# Adafruit_FONA_SIM5320_3G_Breakout.net
KiCad netlist of a schematic drawn in EAGLE
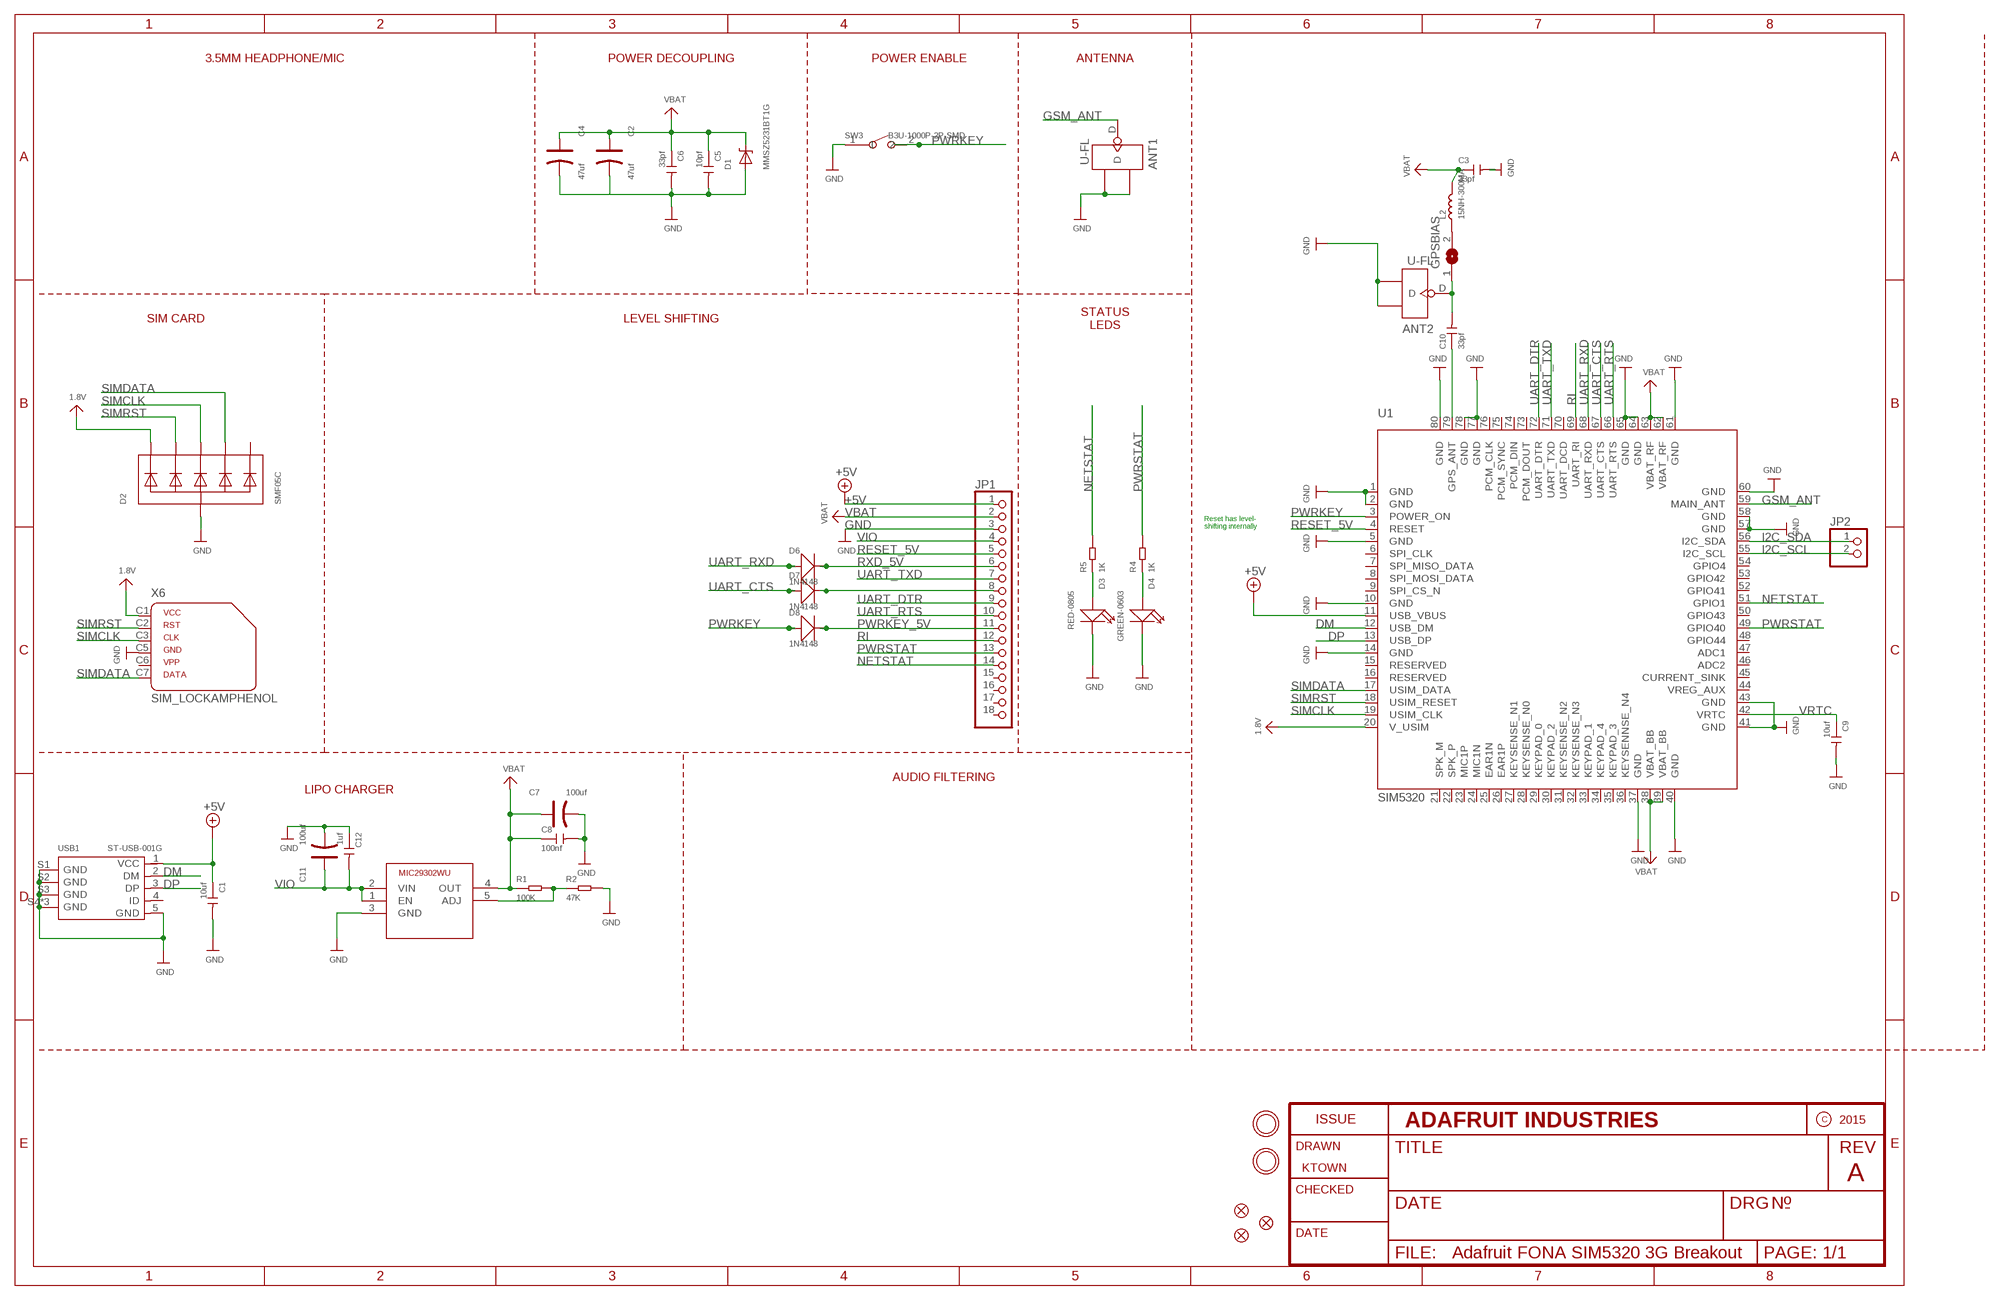
[diagram p0: schematic, sheet 1]

(export (version "E")
  (design (tool "Eeschema 10.0.6"))
  (components
    (comp (ref "ANT1")
      (value "U-FL")
      (footprint "eagle-import:U-FL3P-SMD-2.6X2.6X1.0MM")
      (libsource (lib "eagle-import") (part "ANTENNA-CONN-U-FL(3P)"))
    )
    (comp (ref "ANT2")
      (value "U-FL")
      (footprint "eagle-import:U-FL3P-SMD-2.6X2.6X1.0MM")
      (libsource (lib "eagle-import") (part "ANTENNA-CONN-U-FL(3P)"))
    )
    (comp (ref "C1")
      (value "10uf")
      (footprint "eagle-import:C0603")
      (fields (field (name "MPN") "CC0603KRX5R6BB106"))
      (libsource (lib "eagle-import") (part "CERAMIC-10UF-10V-10%-X5R(0603)"))
    )
    (comp (ref "C2")
      (value "47uf")
      (footprint "eagle-import:AVX-B")
      (fields (field (name "MPN") "TAJB476K010RNJ"))
      (libsource (lib "eagle-import") (part "TANTALUM-SMD-47UF-16V-10%(AVX-B)"))
    )
    (comp (ref "C3")
      (value "33pf")
      (footprint "eagle-import:C0402")
      (fields (field (name "MPN") "CC0402JRNPO9BN330"))
      (libsource (lib "eagle-import") (part "CERAMIC-33PF-50V-5%-NPO(0402)"))
    )
    (comp (ref "C4")
      (value "47uf")
      (footprint "eagle-import:AVX-B")
      (fields (field (name "MPN") "TAJB476K010RNJ"))
      (libsource (lib "eagle-import") (part "TANTALUM-SMD-47UF-16V-10%(AVX-B)"))
    )
    (comp (ref "C5")
      (value "10pf")
      (footprint "eagle-import:C0402")
      (fields (field (name "MPN") "CC0402JRNPO9BN100"))
      (libsource (lib "eagle-import") (part "CERAMIC-10PF-50V-5%-NPO(0402)"))
    )
    (comp (ref "C6")
      (value "33pf")
      (footprint "eagle-import:C0402")
      (fields (field (name "MPN") "CC0402JRNPO9BN330"))
      (libsource (lib "eagle-import") (part "CERAMIC-33PF-50V-5%-NPO(0402)"))
    )
    (comp (ref "C7")
      (value "100uf")
      (footprint "eagle-import:AVX-B")
      (fields (field (name "MPN") "TAJB107M010#NJ"))
      (libsource (lib "eagle-import") (part "TANTALUM-SMD-100UF-10V(AVX-B)"))
    )
    (comp (ref "C8")
      (value "100nf")
      (footprint "eagle-import:C0402")
      (fields (field (name "MPN") "CC0402KRX7R8BB104"))
      (libsource (lib "eagle-import") (part "CERAMIC-100NF-25V-10%-X7R(0402)"))
    )
    (comp (ref "C9")
      (value "10uf")
      (footprint "eagle-import:C0805")
      (fields (field (name "MPN") "CC0805KKX5R8BB106"))
      (libsource (lib "eagle-import") (part "CERAMIC-10UF-25V-10%-X5R(0805)"))
    )
    (comp (ref "C10")
      (value "33pf")
      (footprint "eagle-import:C0402")
      (fields (field (name "MPN") "CC0402JRNPO9BN330"))
      (libsource (lib "eagle-import") (part "CERAMIC-33PF-50V-5%-NPO(0402)"))
    )
    (comp (ref "C11")
      (value "100uf")
      (footprint "eagle-import:AVX-B")
      (fields (field (name "MPN") "TAJB107M010#NJ"))
      (libsource (lib "eagle-import") (part "TANTALUM-SMD-100UF-10V(AVX-B)"))
    )
    (comp (ref "C12")
      (value "1uf")
      (footprint "eagle-import:C0603")
      (fields (field (name "MPN") "CC0603KRX7R8BB105"))
      (libsource (lib "eagle-import") (part "CERAMIC-1UF-25V-10%-X7R(0603)"))
    )
    (comp (ref "D1")
      (value "MMSZ5231BT1G")
      (footprint "eagle-import:SOD-123")
      (libsource (lib "eagle-import") (part "DIODE-ZENERSOD123"))
    )
    (comp (ref "D2")
      (value "SMF05C")
      (footprint "eagle-import:SOT363")
      (libsource (lib "eagle-import") (part "TVSARRAY_5LANE"))
    )
    (comp (ref "D3")
      (value "RED-0805")
      (footprint "eagle-import:LED-0805")
      (fields (field (name "MPN") "17-215SURC/S530-A2/TR8"))
      (libsource (lib "eagle-import") (part "SMD-LED-CLEAR-RED(0805)"))
    )
    (comp (ref "D4")
      (value "GREEN-0603")
      (footprint "eagle-import:LED-0603")
      (fields (field (name "MPN") "19-217-G7C-AN1P2-3T"))
      (libsource (lib "eagle-import") (part "SMD-LED-CLEAR-GREEN(0603)"))
    )
    (comp (ref "D6")
      (value "1N4148")
      (footprint "eagle-import:LL-34")
      (libsource (lib "eagle-import") (part "SMD-DIODE-SWITCH-1N4148(LL-34)"))
    )
    (comp (ref "D7")
      (value "1N4148")
      (footprint "eagle-import:LL-34")
      (libsource (lib "eagle-import") (part "SMD-DIODE-SWITCH-1N4148(LL-34)"))
    )
    (comp (ref "D8")
      (value "1N4148")
      (footprint "eagle-import:LL-34")
      (libsource (lib "eagle-import") (part "SMD-DIODE-SWITCH-1N4148(LL-34)"))
    )
    (comp (ref "FID1")
      (value "FIDUCIAL\"\"")
      (footprint "eagle-import:FIDUCIAL_1MM")
      (libsource (lib "eagle-import") (part "FIDUCIAL{dblquote}{dblquote}"))
    )
    (comp (ref "FID4")
      (value "FIDUCIAL\"\"")
      (footprint "eagle-import:FIDUCIAL_1MM")
      (libsource (lib "eagle-import") (part "FIDUCIAL{dblquote}{dblquote}"))
    )
    (comp (ref "FID5")
      (value "FIDUCIAL\"\"")
      (footprint "eagle-import:FIDUCIAL_1MM")
      (libsource (lib "eagle-import") (part "FIDUCIAL{dblquote}{dblquote}"))
    )
    (comp (ref "GPSBIAS")
      (value "SOLDERJUMPER")
      (footprint "eagle-import:SOLDERJUMPER_ARROW_NOPASTE")
      (libsource (lib "eagle-import") (part "SOLDERJUMPER"))
    )
    (comp (ref "IC1")
      (value "MIC29302WU")
      (footprint "eagle-import:TO263-5")
      (fields (field (name "MF") "Microchip"))
      (libsource (lib "eagle-import") (part "MIC29302WU"))
    )
    (comp (ref "JP1")
      (value "HEADER-1X18")
      (footprint "eagle-import:1X18_ROUND70")
      (libsource (lib "eagle-import") (part "HEADER-1X18"))
    )
    (comp (ref "JP2")
      (value "HEADER-1X2ROUND")
      (footprint "eagle-import:1X02_ROUND")
      (libsource (lib "eagle-import") (part "HEADER-1X2ROUND"))
    )
    (comp (ref "L2")
      (value "15NH-300MA")
      (footprint "eagle-import:L0402")
      (fields (field (name "MPN") "LQG15HS15NJ02"))
      (libsource (lib "eagle-import") (part "SMD-INDUCTOR-15NH-5%-300MA(0402)"))
    )
    (comp (ref "R1")
      (value "100K")
      (footprint "eagle-import:R0603")
      (fields (field (name "MPN") "RC0603FR-07100KL"))
      (libsource (lib "eagle-import") (part "SMD-RES-100K-1%-1/10W(0603)"))
    )
    (comp (ref "R2")
      (value "47K")
      (footprint "eagle-import:R0603")
      (fields (field (name "MPN") "RC0603JR-0747KL"))
      (libsource (lib "eagle-import") (part "SMD-RES-47K-5%-1/10W(0603)"))
    )
    (comp (ref "R4")
      (value "1K")
      (footprint "eagle-import:R0603")
      (fields (field (name "MPN") "RC0603FR-071KL"))
      (libsource (lib "eagle-import") (part "SMD-RES-1K-1%-1/10W(0603)"))
    )
    (comp (ref "R5")
      (value "1K")
      (footprint "eagle-import:R0603")
      (fields (field (name "MPN") "RC0603FR-071KL"))
      (libsource (lib "eagle-import") (part "SMD-RES-1K-1%-1/10W(0603)"))
    )
    (comp (ref "SW3")
      (value "B3U-1000P-2P-SMD")
      (footprint "eagle-import:SW2-2.6-3.0X2.5X1.2+0.4MM")
      (libsource (lib "eagle-import") (part "SMD-BUTTON(2P-3.0X2.5X1.2+0.4MM)-B3U-1000P-2P-SMD"))
    )
    (comp (ref "U$33")
      (value "MOUNTINGHOLE2.5")
      (footprint "eagle-import:MOUNTINGHOLE_2.5_PLATED")
      (libsource (lib "eagle-import") (part "MOUNTINGHOLE2.5"))
    )
    (comp (ref "U$34")
      (value "MOUNTINGHOLE2.5")
      (footprint "eagle-import:MOUNTINGHOLE_2.5_PLATED")
      (libsource (lib "eagle-import") (part "MOUNTINGHOLE2.5"))
    )
    (comp (ref "U1")
      (value "SIM5320")
      (footprint "eagle-import:SIM5320")
      (libsource (lib "eagle-import") (part "GSM_SIM5320_LITERAL"))
    )
    (comp (ref "USB1")
      (value "ST-USB-001G")
      (footprint "eagle-import:MICRO-USB5+4P-SMD-0.65-B")
      (libsource (lib "eagle-import") (part "MICRO-USB-SMD-B-WITHOUT-POST-W/P(ST-USB-001G)"))
    )
    (comp (ref "X6")
      (value "SIM_LOCKAMPHENOL")
      (footprint "eagle-import:C707_10M006_512_2")
      (libsource (lib "eagle-import") (part "SIM_LOCKAMPHENOL"))
    )
  )
  (nets
    (net (code "1") (name "+5V") (class "Default")
      (node (ref "C1") (pin "1") (pinfunction "1_1") (pintype "passive"))
      (node (ref "JP1") (pin "1") (pinfunction "1_1") (pintype "passive"))
      (node (ref "U1") (pin "11") (pinfunction "USB_VBUS_11") (pintype "bidirectional"))
      (node (ref "USB1") (pin "1") (pinfunction "VCC_1") (pintype "bidirectional"))
    )
    (net (code "2") (name "/DM") (class "Default")
      (node (ref "U1") (pin "12") (pinfunction "USB_DM_12") (pintype "bidirectional"))
      (node (ref "USB1") (pin "2") (pinfunction "DM_2") (pintype "bidirectional"))
    )
    (net (code "3") (name "/DP") (class "Default")
      (node (ref "U1") (pin "13") (pinfunction "USB_DP_13") (pintype "bidirectional"))
      (node (ref "USB1") (pin "3") (pinfunction "DP_3") (pintype "bidirectional"))
    )
    (net (code "4") (name "/GSM_ANT") (class "Default")
      (node (ref "ANT1") (pin "D") (pinfunction "D_D") (pintype "bidirectional"))
      (node (ref "U1") (pin "59") (pinfunction "MAIN_ANT_59") (pintype "bidirectional"))
    )
    (net (code "5") (name "/I2C_SCL") (class "Default")
      (node (ref "JP2") (pin "2") (pinfunction "2_2") (pintype "passive"))
      (node (ref "U1") (pin "55") (pinfunction "I2C_SCL_55") (pintype "bidirectional"))
    )
    (net (code "6") (name "/I2C_SDA") (class "Default")
      (node (ref "JP2") (pin "1") (pinfunction "1_1") (pintype "passive"))
      (node (ref "U1") (pin "56") (pinfunction "I2C_SDA_56") (pintype "bidirectional"))
    )
    (net (code "7") (name "/NETSTAT") (class "Default")
      (node (ref "JP1") (pin "14") (pinfunction "14_14") (pintype "passive"))
      (node (ref "R5") (pin "2") (pinfunction "2_2") (pintype "passive"))
      (node (ref "U1") (pin "51") (pinfunction "GPIO1_51") (pintype "bidirectional"))
    )
    (net (code "8") (name "/PWRKEY") (class "Default")
      (node (ref "D8") (pin "A") (pinfunction "+_A") (pintype "passive"))
      (node (ref "SW3") (pin "2") (pinfunction "2_2") (pintype "bidirectional"))
      (node (ref "U1") (pin "3") (pinfunction "POWER_ON_3") (pintype "bidirectional"))
    )
    (net (code "9") (name "/PWRKEY_5V") (class "Default")
      (node (ref "D8") (pin "C") (pinfunction "-_C") (pintype "passive"))
      (node (ref "JP1") (pin "11") (pinfunction "11_11") (pintype "passive"))
    )
    (net (code "10") (name "/PWRSTAT") (class "Default")
      (node (ref "JP1") (pin "13") (pinfunction "13_13") (pintype "passive"))
      (node (ref "R4") (pin "2") (pinfunction "2_2") (pintype "passive"))
      (node (ref "U1") (pin "49") (pinfunction "GPIO40_49") (pintype "bidirectional"))
    )
    (net (code "11") (name "/RESET_5V") (class "Default")
      (node (ref "JP1") (pin "5") (pinfunction "5_5") (pintype "passive"))
      (node (ref "U1") (pin "4") (pinfunction "RESET_4") (pintype "bidirectional"))
    )
    (net (code "12") (name "/RI") (class "Default")
      (node (ref "JP1") (pin "12") (pinfunction "12_12") (pintype "passive"))
      (node (ref "U1") (pin "69") (pinfunction "UART_RI_69") (pintype "bidirectional"))
    )
    (net (code "13") (name "/RXD_5V") (class "Default")
      (node (ref "D6") (pin "C") (pinfunction "-_C") (pintype "passive"))
      (node (ref "JP1") (pin "6") (pinfunction "6_6") (pintype "passive"))
    )
    (net (code "14") (name "/SIMCLK") (class "Default")
      (node (ref "D2") (pin "4") (pinfunction "C3_4") (pintype "passive"))
      (node (ref "U1") (pin "19") (pinfunction "USIM_CLK_19") (pintype "bidirectional"))
      (node (ref "X6") (pin "C3") (pinfunction "3_C3") (pintype "passive"))
    )
    (net (code "15") (name "/SIMDATA") (class "Default")
      (node (ref "D2") (pin "5") (pinfunction "C4_5") (pintype "passive"))
      (node (ref "U1") (pin "17") (pinfunction "USIM_DATA_17") (pintype "bidirectional"))
      (node (ref "X6") (pin "C7") (pinfunction "6_C7") (pintype "passive"))
    )
    (net (code "16") (name "/SIMRST") (class "Default")
      (node (ref "D2") (pin "3") (pinfunction "C2_3") (pintype "passive"))
      (node (ref "U1") (pin "18") (pinfunction "USIM_RESET_18") (pintype "bidirectional"))
      (node (ref "X6") (pin "C2") (pinfunction "2_C2") (pintype "passive"))
    )
    (net (code "17") (name "/UART_CTS") (class "Default")
      (node (ref "D7") (pin "A") (pinfunction "+_A") (pintype "passive"))
      (node (ref "U1") (pin "67") (pinfunction "UART_CTS_67") (pintype "bidirectional"))
    )
    (net (code "18") (name "/UART_DTR") (class "Default")
      (node (ref "JP1") (pin "9") (pinfunction "9_9") (pintype "passive"))
      (node (ref "U1") (pin "72") (pinfunction "UART_DTR_72") (pintype "bidirectional"))
    )
    (net (code "19") (name "/UART_RTS") (class "Default")
      (node (ref "JP1") (pin "10") (pinfunction "10_10") (pintype "passive"))
      (node (ref "U1") (pin "66") (pinfunction "UART_RTS_66") (pintype "bidirectional"))
    )
    (net (code "20") (name "/UART_RXD") (class "Default")
      (node (ref "D6") (pin "A") (pinfunction "+_A") (pintype "passive"))
      (node (ref "U1") (pin "68") (pinfunction "UART_RXD_68") (pintype "bidirectional"))
    )
    (net (code "21") (name "/UART_TXD") (class "Default")
      (node (ref "JP1") (pin "7") (pinfunction "7_7") (pintype "passive"))
      (node (ref "U1") (pin "71") (pinfunction "UART_TXD_71") (pintype "bidirectional"))
    )
    (net (code "22") (name "/VIO") (class "Default")
      (node (ref "C11") (pin "+") (pinfunction "+_+") (pintype "passive"))
      (node (ref "C12") (pin "2") (pinfunction "2_2") (pintype "passive"))
      (node (ref "IC1") (pin "1") (pinfunction "EN_1") (pintype "bidirectional"))
      (node (ref "IC1") (pin "2") (pinfunction "VIN_2") (pintype "bidirectional"))
      (node (ref "JP1") (pin "4") (pinfunction "4_4") (pintype "passive"))
    )
    (net (code "23") (name "/VRTC") (class "Default")
      (node (ref "C9") (pin "1") (pinfunction "1_1") (pintype "passive"))
      (node (ref "U1") (pin "42") (pinfunction "VRTC_42") (pintype "bidirectional"))
    )
    (net (code "24") (name "1.8V") (class "Default")
      (node (ref "D2") (pin "1") (pinfunction "C1_1") (pintype "passive"))
      (node (ref "U1") (pin "20") (pinfunction "V_USIM_20") (pintype "bidirectional"))
      (node (ref "X6") (pin "C1") (pinfunction "1_C1") (pintype "passive"))
    )
    (net (code "25") (name "GND") (class "Default")
      (node (ref "ANT1") (pin "GND1") (pinfunction "GND1_GND1") (pintype "bidirectional"))
      (node (ref "ANT1") (pin "GND2") (pinfunction "GND2_GND2") (pintype "bidirectional"))
      (node (ref "ANT2") (pin "GND1") (pinfunction "GND1_GND1") (pintype "bidirectional"))
      (node (ref "ANT2") (pin "GND2") (pinfunction "GND2_GND2") (pintype "bidirectional"))
      (node (ref "C1") (pin "2") (pinfunction "2_2") (pintype "passive"))
      (node (ref "C11") (pin "-") (pinfunction "-_-") (pintype "passive"))
      (node (ref "C12") (pin "1") (pinfunction "1_1") (pintype "passive"))
      (node (ref "C2") (pin "-") (pinfunction "-_-") (pintype "passive"))
      (node (ref "C3") (pin "2") (pinfunction "2_2") (pintype "passive"))
      (node (ref "C4") (pin "-") (pinfunction "-_-") (pintype "passive"))
      (node (ref "C5") (pin "2") (pinfunction "2_2") (pintype "passive"))
      (node (ref "C6") (pin "2") (pinfunction "2_2") (pintype "passive"))
      (node (ref "C7") (pin "-") (pinfunction "-_-") (pintype "passive"))
      (node (ref "C8") (pin "2") (pinfunction "2_2") (pintype "passive"))
      (node (ref "C9") (pin "2") (pinfunction "2_2") (pintype "passive"))
      (node (ref "D1") (pin "A") (pinfunction "A_A") (pintype "passive"))
      (node (ref "D2") (pin "2") (pinfunction "A_2") (pintype "passive"))
      (node (ref "D3") (pin "-") (pinfunction "-_-") (pintype "passive"))
      (node (ref "D4") (pin "-") (pinfunction "-_-") (pintype "passive"))
      (node (ref "IC1") (pin "3") (pinfunction "GND_3") (pintype "bidirectional"))
      (node (ref "JP1") (pin "3") (pinfunction "3_3") (pintype "passive"))
      (node (ref "R2") (pin "2") (pinfunction "2_2") (pintype "passive"))
      (node (ref "SW3") (pin "1") (pinfunction "1_1") (pintype "bidirectional"))
      (node (ref "U1") (pin "1") (pinfunction "GND_1") (pintype "bidirectional"))
      (node (ref "U1") (pin "10") (pinfunction "GND_10") (pintype "bidirectional"))
      (node (ref "U1") (pin "14") (pinfunction "GND_14") (pintype "bidirectional"))
      (node (ref "U1") (pin "2") (pinfunction "GND_2") (pintype "bidirectional"))
      (node (ref "U1") (pin "37") (pinfunction "GND_37") (pintype "bidirectional"))
      (node (ref "U1") (pin "40") (pinfunction "GND_40") (pintype "bidirectional"))
      (node (ref "U1") (pin "41") (pinfunction "GND_41") (pintype "bidirectional"))
      (node (ref "U1") (pin "43") (pinfunction "GND_43") (pintype "bidirectional"))
      (node (ref "U1") (pin "5") (pinfunction "GND_5") (pintype "bidirectional"))
      (node (ref "U1") (pin "57") (pinfunction "GND_57") (pintype "bidirectional"))
      (node (ref "U1") (pin "58") (pinfunction "GND_58") (pintype "bidirectional"))
      (node (ref "U1") (pin "60") (pinfunction "GND_60") (pintype "bidirectional"))
      (node (ref "U1") (pin "61") (pinfunction "GND_61") (pintype "bidirectional"))
      (node (ref "U1") (pin "64") (pinfunction "GND_64") (pintype "bidirectional"))
      (node (ref "U1") (pin "65") (pinfunction "GND_65") (pintype "bidirectional"))
      (node (ref "U1") (pin "77") (pinfunction "GND_77") (pintype "bidirectional"))
      (node (ref "U1") (pin "78") (pinfunction "GND_78") (pintype "bidirectional"))
      (node (ref "U1") (pin "80") (pinfunction "GND_80") (pintype "bidirectional"))
      (node (ref "USB1") (pin "5") (pinfunction "GND_5") (pintype "bidirectional"))
      (node (ref "USB1") (pin "S1") (pinfunction "GND_S1") (pintype "bidirectional"))
      (node (ref "USB1") (pin "S2") (pinfunction "GND_S2") (pintype "bidirectional"))
      (node (ref "USB1") (pin "S3") (pinfunction "GND_S3") (pintype "bidirectional"))
      (node (ref "USB1") (pin "S4") (pinfunction "GND_S4") (pintype "bidirectional"))
      (node (ref "USB1") (pin "S5") (pinfunction "GND_S5") (pintype "bidirectional"))
      (node (ref "USB1") (pin "S6") (pinfunction "GND_S6") (pintype "bidirectional"))
      (node (ref "X6") (pin "C5") (pinfunction "4_C5") (pintype "passive"))
    )
    (net (code "26") (name "Net-(ANT2-PadD)") (class "Default")
      (node (ref "ANT2") (pin "D") (pinfunction "D_D") (pintype "bidirectional"))
      (node (ref "C10") (pin "2") (pinfunction "2_2") (pintype "passive"))
      (node (ref "GPSBIAS") (pin "1") (pinfunction "1_1") (pintype "passive"))
    )
    (net (code "27") (name "Net-(D3-Pad+)") (class "Default")
      (node (ref "D3") (pin "+") (pinfunction "+_+") (pintype "passive"))
      (node (ref "R5") (pin "1") (pinfunction "1_1") (pintype "passive"))
    )
    (net (code "28") (name "Net-(D4-Pad+)") (class "Default")
      (node (ref "D4") (pin "+") (pinfunction "+_+") (pintype "passive"))
      (node (ref "R4") (pin "1") (pinfunction "1_1") (pintype "passive"))
    )
    (net (code "29") (name "Net-(D7--)") (class "Default")
      (node (ref "D7") (pin "C") (pinfunction "-_C") (pintype "passive"))
      (node (ref "JP1") (pin "8") (pinfunction "8_8") (pintype "passive"))
    )
    (net (code "30") (name "Net-(GPSBIAS-Pad2)") (class "Default")
      (node (ref "GPSBIAS") (pin "2") (pinfunction "2_2") (pintype "passive"))
      (node (ref "L2") (pin "1") (pinfunction "1_1") (pintype "passive"))
    )
    (net (code "31") (name "Net-(IC1-ADJ)") (class "Default")
      (node (ref "IC1") (pin "5") (pinfunction "ADJ_5") (pintype "bidirectional"))
      (node (ref "R1") (pin "2") (pinfunction "2_2") (pintype "passive"))
      (node (ref "R2") (pin "1") (pinfunction "1_1") (pintype "passive"))
    )
    (net (code "32") (name "Net-(U1-GPS_ANT)") (class "Default")
      (node (ref "C10") (pin "1") (pinfunction "1_1") (pintype "passive"))
      (node (ref "U1") (pin "79") (pinfunction "GPS_ANT_79") (pintype "bidirectional"))
    )
    (net (code "33") (name "VBAT") (class "Default")
      (node (ref "C2") (pin "+") (pinfunction "+_+") (pintype "passive"))
      (node (ref "C3") (pin "1") (pinfunction "1_1") (pintype "passive"))
      (node (ref "C4") (pin "+") (pinfunction "+_+") (pintype "passive"))
      (node (ref "C5") (pin "1") (pinfunction "1_1") (pintype "passive"))
      (node (ref "C6") (pin "1") (pinfunction "1_1") (pintype "passive"))
      (node (ref "C7") (pin "+") (pinfunction "+_+") (pintype "passive"))
      (node (ref "C8") (pin "1") (pinfunction "1_1") (pintype "passive"))
      (node (ref "D1") (pin "C") (pinfunction "C_C") (pintype "passive"))
      (node (ref "IC1") (pin "4") (pinfunction "OUT_4") (pintype "bidirectional"))
      (node (ref "JP1") (pin "2") (pinfunction "2_2") (pintype "passive"))
      (node (ref "L2") (pin "2") (pinfunction "2_2") (pintype "passive"))
      (node (ref "R1") (pin "1") (pinfunction "1_1") (pintype "passive"))
      (node (ref "U1") (pin "38") (pinfunction "VBAT_BB_38") (pintype "bidirectional"))
      (node (ref "U1") (pin "39") (pinfunction "VBAT_BB_39") (pintype "bidirectional"))
      (node (ref "U1") (pin "62") (pinfunction "VBAT_RF_62") (pintype "bidirectional"))
      (node (ref "U1") (pin "63") (pinfunction "VBAT_RF_63") (pintype "bidirectional"))
    )
    (net (code "34") (name "unconnected-(D2-C5-Pad6)") (class "Default")
      (node (ref "D2") (pin "6") (pinfunction "C5_6") (pintype "passive"))
    )
    (net (code "35") (name "unconnected-(JP1-Pad15)") (class "Default")
      (node (ref "JP1") (pin "15") (pinfunction "15_15") (pintype "passive"))
    )
    (net (code "36") (name "unconnected-(JP1-Pad16)") (class "Default")
      (node (ref "JP1") (pin "16") (pinfunction "16_16") (pintype "passive"))
    )
    (net (code "37") (name "unconnected-(JP1-Pad17)") (class "Default")
      (node (ref "JP1") (pin "17") (pinfunction "17_17") (pintype "passive"))
    )
    (net (code "38") (name "unconnected-(JP1-Pad18)") (class "Default")
      (node (ref "JP1") (pin "18") (pinfunction "18_18") (pintype "passive"))
    )
    (net (code "39") (name "unconnected-(U1-ADC1-Pad47)") (class "Default")
      (node (ref "U1") (pin "47") (pinfunction "ADC1_47") (pintype "bidirectional"))
    )
    (net (code "40") (name "unconnected-(U1-ADC2-Pad46)") (class "Default")
      (node (ref "U1") (pin "46") (pinfunction "ADC2_46") (pintype "bidirectional"))
    )
    (net (code "41") (name "unconnected-(U1-CURRENT_SINK-Pad45)") (class "Default")
      (node (ref "U1") (pin "45") (pinfunction "CURRENT_SINK_45") (pintype "bidirectional"))
    )
    (net (code "42") (name "unconnected-(U1-EAR1N-Pad25)") (class "Default")
      (node (ref "U1") (pin "25") (pinfunction "EAR1N_25") (pintype "bidirectional"))
    )
    (net (code "43") (name "unconnected-(U1-EAR1P-Pad26)") (class "Default")
      (node (ref "U1") (pin "26") (pinfunction "EAR1P_26") (pintype "bidirectional"))
    )
    (net (code "44") (name "unconnected-(U1-GPIO4-Pad54)") (class "Default")
      (node (ref "U1") (pin "54") (pinfunction "GPIO4_54") (pintype "bidirectional"))
    )
    (net (code "45") (name "unconnected-(U1-GPIO41-Pad52)") (class "Default")
      (node (ref "U1") (pin "52") (pinfunction "GPIO41_52") (pintype "bidirectional"))
    )
    (net (code "46") (name "unconnected-(U1-GPIO42-Pad53)") (class "Default")
      (node (ref "U1") (pin "53") (pinfunction "GPIO42_53") (pintype "bidirectional"))
    )
    (net (code "47") (name "unconnected-(U1-GPIO43-Pad50)") (class "Default")
      (node (ref "U1") (pin "50") (pinfunction "GPIO43_50") (pintype "bidirectional"))
    )
    (net (code "48") (name "unconnected-(U1-GPIO44-Pad48)") (class "Default")
      (node (ref "U1") (pin "48") (pinfunction "GPIO44_48") (pintype "bidirectional"))
    )
    (net (code "49") (name "unconnected-(U1-KEYPAD_0-Pad29)") (class "Default")
      (node (ref "U1") (pin "29") (pinfunction "KEYPAD_0_29") (pintype "bidirectional"))
    )
    (net (code "50") (name "unconnected-(U1-KEYPAD_1-Pad33)") (class "Default")
      (node (ref "U1") (pin "33") (pinfunction "KEYPAD_1_33") (pintype "bidirectional"))
    )
    (net (code "51") (name "unconnected-(U1-KEYPAD_2-Pad30)") (class "Default")
      (node (ref "U1") (pin "30") (pinfunction "KEYPAD_2_30") (pintype "bidirectional"))
    )
    (net (code "52") (name "unconnected-(U1-KEYPAD_3-Pad35)") (class "Default")
      (node (ref "U1") (pin "35") (pinfunction "KEYPAD_3_35") (pintype "bidirectional"))
    )
    (net (code "53") (name "unconnected-(U1-KEYPAD_4-Pad34)") (class "Default")
      (node (ref "U1") (pin "34") (pinfunction "KEYPAD_4_34") (pintype "bidirectional"))
    )
    (net (code "54") (name "unconnected-(U1-KEYSENNSE_N4-Pad36)") (class "Default")
      (node (ref "U1") (pin "36") (pinfunction "KEYSENNSE_N4_36") (pintype "bidirectional"))
    )
    (net (code "55") (name "unconnected-(U1-KEYSENSE_N0-Pad28)") (class "Default")
      (node (ref "U1") (pin "28") (pinfunction "KEYSENSE_N0_28") (pintype "bidirectional"))
    )
    (net (code "56") (name "unconnected-(U1-KEYSENSE_N1-Pad27)") (class "Default")
      (node (ref "U1") (pin "27") (pinfunction "KEYSENSE_N1_27") (pintype "bidirectional"))
    )
    (net (code "57") (name "unconnected-(U1-KEYSENSE_N2-Pad31)") (class "Default")
      (node (ref "U1") (pin "31") (pinfunction "KEYSENSE_N2_31") (pintype "bidirectional"))
    )
    (net (code "58") (name "unconnected-(U1-KEYSENSE_N3-Pad32)") (class "Default")
      (node (ref "U1") (pin "32") (pinfunction "KEYSENSE_N3_32") (pintype "bidirectional"))
    )
    (net (code "59") (name "unconnected-(U1-MIC1N-Pad24)") (class "Default")
      (node (ref "U1") (pin "24") (pinfunction "MIC1N_24") (pintype "bidirectional"))
    )
    (net (code "60") (name "unconnected-(U1-MIC1P-Pad23)") (class "Default")
      (node (ref "U1") (pin "23") (pinfunction "MIC1P_23") (pintype "bidirectional"))
    )
    (net (code "61") (name "unconnected-(U1-PCM_CLK-Pad76)") (class "Default")
      (node (ref "U1") (pin "76") (pinfunction "PCM_CLK_76") (pintype "bidirectional"))
    )
    (net (code "62") (name "unconnected-(U1-PCM_DIN-Pad74)") (class "Default")
      (node (ref "U1") (pin "74") (pinfunction "PCM_DIN_74") (pintype "bidirectional"))
    )
    (net (code "63") (name "unconnected-(U1-PCM_DOUT-Pad73)") (class "Default")
      (node (ref "U1") (pin "73") (pinfunction "PCM_DOUT_73") (pintype "bidirectional"))
    )
    (net (code "64") (name "unconnected-(U1-PCM_SYNC-Pad75)") (class "Default")
      (node (ref "U1") (pin "75") (pinfunction "PCM_SYNC_75") (pintype "bidirectional"))
    )
    (net (code "65") (name "unconnected-(U1-RESERVED-Pad15)") (class "Default")
      (node (ref "U1") (pin "15") (pinfunction "RESERVED_15") (pintype "bidirectional"))
    )
    (net (code "66") (name "unconnected-(U1-RESERVED-Pad16)") (class "Default")
      (node (ref "U1") (pin "16") (pinfunction "RESERVED_16") (pintype "bidirectional"))
    )
    (net (code "67") (name "unconnected-(U1-SPI_CLK-Pad6)") (class "Default")
      (node (ref "U1") (pin "6") (pinfunction "SPI_CLK_6") (pintype "bidirectional"))
    )
    (net (code "68") (name "unconnected-(U1-SPI_CS_N-Pad9)") (class "Default")
      (node (ref "U1") (pin "9") (pinfunction "SPI_CS_N_9") (pintype "bidirectional"))
    )
    (net (code "69") (name "unconnected-(U1-SPI_MISO_DATA-Pad7)") (class "Default")
      (node (ref "U1") (pin "7") (pinfunction "SPI_MISO_DATA_7") (pintype "bidirectional"))
    )
    (net (code "70") (name "unconnected-(U1-SPI_MOSI_DATA-Pad8)") (class "Default")
      (node (ref "U1") (pin "8") (pinfunction "SPI_MOSI_DATA_8") (pintype "bidirectional"))
    )
    (net (code "71") (name "unconnected-(U1-SPK_M-Pad21)") (class "Default")
      (node (ref "U1") (pin "21") (pinfunction "SPK_M_21") (pintype "bidirectional"))
    )
    (net (code "72") (name "unconnected-(U1-SPK_P-Pad22)") (class "Default")
      (node (ref "U1") (pin "22") (pinfunction "SPK_P_22") (pintype "bidirectional"))
    )
    (net (code "73") (name "unconnected-(U1-UART_DCD-Pad70)") (class "Default")
      (node (ref "U1") (pin "70") (pinfunction "UART_DCD_70") (pintype "bidirectional"))
    )
    (net (code "74") (name "unconnected-(U1-VREG_AUX-Pad44)") (class "Default")
      (node (ref "U1") (pin "44") (pinfunction "VREG_AUX_44") (pintype "bidirectional"))
    )
    (net (code "75") (name "unconnected-(USB1-ID-Pad4)") (class "Default")
      (node (ref "USB1") (pin "4") (pinfunction "ID_4") (pintype "bidirectional"))
    )
    (net (code "76") (name "unconnected-(X6-5-PadC6)") (class "Default")
      (node (ref "X6") (pin "C6") (pinfunction "5_C6") (pintype "passive"))
    )
  )
)
